# LoRaWAN_Senior_Project_Schematic.net
KiCad netlist of a schematic drawn in Altium Designer
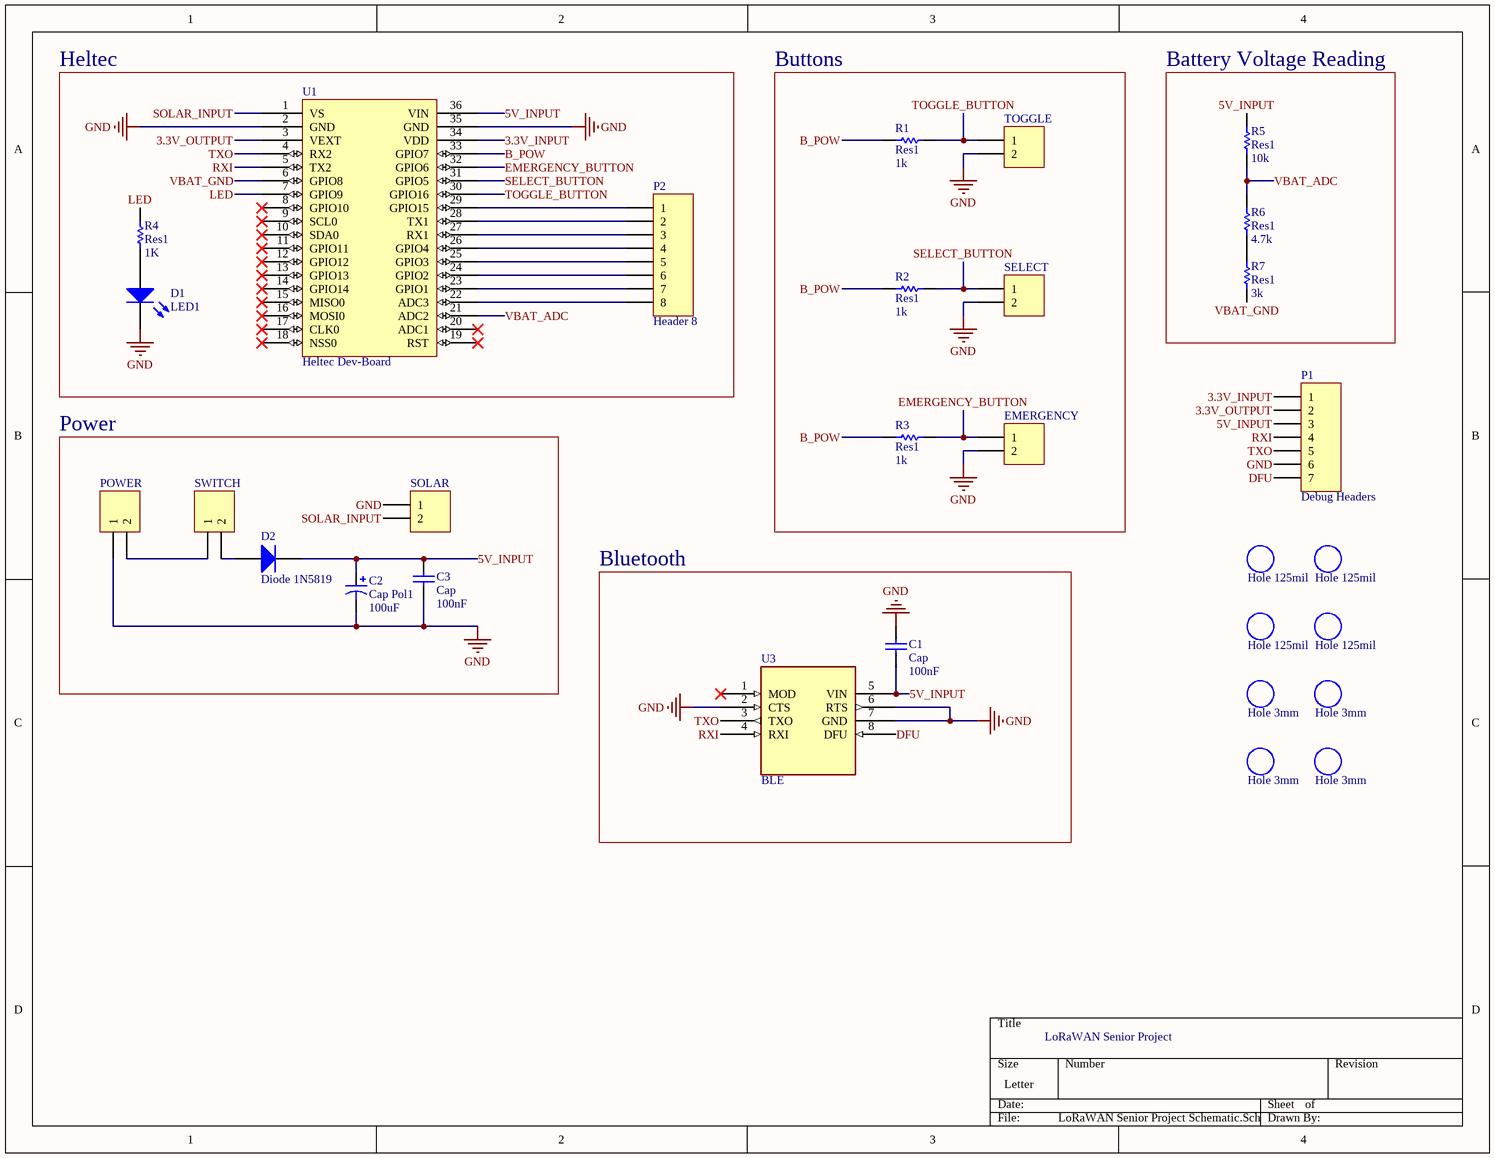
[diagram p0: LoRaWAN Senior Project Schematic.SchDoc]

(export (version "E")
  (design (tool "Eeschema 10.0.6"))
  (components
    (comp (ref "C1")
      (value "Cap")
      (footprint "RAD-0.1")
      (description "Capacitor")
      (fields (field (name "ALTIUM_VALUE") "100nF") (field (name "PUBLISHER") "Altium Limited"))
      (libsource (lib "Miscellaneous Devices") (part "Cap"))
    )
    (comp (ref "C2")
      (value "Cap Pol1")
      (footprint "RAD-0.2")
      (description "Polarized Capacitor (Radial)")
      (fields (field (name "ALTIUM_VALUE") "100uF") (field (name "PUBLISHER") "Altium Limited"))
      (libsource (lib "Miscellaneous Devices") (part "Cap Pol1"))
    )
    (comp (ref "C3")
      (value "Cap")
      (footprint "RAD-0.1")
      (description "Capacitor")
      (fields (field (name "ALTIUM_VALUE") "100nF") (field (name "PUBLISHER") "Altium Limited"))
      (libsource (lib "Miscellaneous Devices") (part "Cap"))
    )
    (comp (ref "D1")
      (value "LED1")
      (footprint "LED-1")
      (description "Typical RED GaAs LED")
      (fields (field (name "PUBLISHER") "Altium Limited"))
      (libsource (lib "Miscellaneous Devices") (part "LED1"))
    )
    (comp (ref "D2")
      (value "Diode 1N5819")
      (footprint "DO-41")
      (description "1 Amp General Purpose Rectifier")
      (fields (field (name "PUBLISHER") "Altium Limited"))
      (libsource (lib "Miscellaneous Devices") (part "Diode 1N4001"))
    )
    (comp (ref "EMERGENCY")
      (value "Button Port")
      (footprint "CON2screw")
      (libsource (lib "ECE Lib 22") (part "Power"))
    )
    (comp (ref "H1")
      (value "Hole 125mil")
      (footprint "Hole 125mil")
      (libsource (lib "ECE Lib 22") (part "Hole 125mil"))
    )
    (comp (ref "H2")
      (value "Hole 125mil")
      (footprint "Hole 125mil")
      (libsource (lib "ECE Lib 22") (part "Hole 125mil"))
    )
    (comp (ref "H3")
      (value "Hole 125mil")
      (footprint "Hole 125mil")
      (libsource (lib "ECE Lib 22") (part "Hole 125mil"))
    )
    (comp (ref "H4")
      (value "Hole 125mil")
      (footprint "Hole 125mil")
      (libsource (lib "ECE Lib 22") (part "Hole 125mil"))
    )
    (comp (ref "H5")
      (value "Hole 3mm")
      (footprint "Hole 3mm")
      (libsource (lib "ECE Lib 22") (part "Hole 3mm"))
    )
    (comp (ref "H6")
      (value "Hole 3mm")
      (footprint "Hole 3mm")
      (libsource (lib "ECE Lib 22") (part "Hole 3mm"))
    )
    (comp (ref "H7")
      (value "Hole 3mm")
      (footprint "Hole 3mm")
      (libsource (lib "ECE Lib 22") (part "Hole 3mm"))
    )
    (comp (ref "H8")
      (value "Hole 3mm")
      (footprint "Hole 3mm")
      (libsource (lib "ECE Lib 22") (part "Hole 3mm"))
    )
    (comp (ref "P1")
      (value "Debug Headers")
      (footprint "HDR1X7")
      (description "Header, 7-Pin")
      (fields (field (name "PUBLISHER") "Altium Limited"))
      (libsource (lib "Miscellaneous Connectors") (part "Header 7"))
    )
    (comp (ref "P2")
      (value "Header 8")
      (footprint "HDR1X8")
      (description "Header, 8-Pin")
      (fields (field (name "PUBLISHER") "Altium Limited"))
      (libsource (lib "Miscellaneous Connectors") (part "Header 8"))
    )
    (comp (ref "POWER") (value "Power Port") (footprint "CON2screw") (libsource (lib "") (part "Power_1")))
    (comp (ref "R1")
      (value "Res1")
      (footprint "RESISTOR")
      (description "Resistor")
      (fields (field (name "ALTIUM_VALUE") "1k") (field (name "PUBLISHER") "Altium Limited"))
      (libsource (lib "Miscellaneous Devices") (part "Res1"))
    )
    (comp (ref "R2")
      (value "Res1")
      (footprint "RESISTOR")
      (description "Resistor")
      (fields (field (name "ALTIUM_VALUE") "1k") (field (name "PUBLISHER") "Altium Limited"))
      (libsource (lib "Miscellaneous Devices") (part "Res1"))
    )
    (comp (ref "R3")
      (value "Res1")
      (footprint "RESISTOR")
      (description "Resistor")
      (fields (field (name "ALTIUM_VALUE") "1k") (field (name "PUBLISHER") "Altium Limited"))
      (libsource (lib "Miscellaneous Devices") (part "Res1"))
    )
    (comp (ref "R4")
      (value "Res1")
      (footprint "AXIAL-0.3")
      (description "Resistor")
      (fields (field (name "ALTIUM_VALUE") "1K") (field (name "PUBLISHER") "Altium Limited"))
      (libsource (lib "Miscellaneous Devices") (part "Res1"))
    )
    (comp (ref "R5")
      (value "Res1")
      (footprint "RESISTOR")
      (description "Resistor")
      (fields (field (name "ALTIUM_VALUE") "10k") (field (name "PUBLISHER") "Altium Limited"))
      (libsource (lib "Miscellaneous Devices") (part "Res1"))
    )
    (comp (ref "R6")
      (value "Res1")
      (footprint "RESISTOR")
      (description "Resistor")
      (fields (field (name "ALTIUM_VALUE") "4.7k") (field (name "PUBLISHER") "Altium Limited"))
      (libsource (lib "Miscellaneous Devices") (part "Res1"))
    )
    (comp (ref "R7")
      (value "Res1")
      (footprint "RESISTOR")
      (description "Resistor")
      (fields (field (name "ALTIUM_VALUE") "3k") (field (name "PUBLISHER") "Altium Limited"))
      (libsource (lib "Miscellaneous Devices") (part "Res1"))
    )
    (comp (ref "SELECT")
      (value "Button Port")
      (footprint "CON2screw")
      (libsource (lib "ECE Lib 22") (part "Power"))
    )
    (comp (ref "SOLAR")
      (value "Solar Port")
      (footprint "CON2screw")
      (libsource (lib "ECE Lib 22") (part "Power"))
    )
    (comp (ref "SWITCH") (value "Switch Port") (footprint "CON2screw") (libsource (lib "") (part "Power_1")))
    (comp (ref "TOGGLE")
      (value "Button Port")
      (footprint "CON2screw")
      (libsource (lib "ECE Lib 22") (part "Power"))
    )
    (comp (ref "U1")
      (value "Heltec Dev-Board")
      (footprint "HELTEC")
      (libsource (lib "Senior Design SCHLIB") (part "Heltec Dev-Board"))
    )
    (comp (ref "U3")
      (value "BLE")
      (footprint "Adafruit BLE")
      (libsource (lib "Senior Design SCHLIB") (part "Adafruit BLE"))
    )
  )
  (nets
    (net (code "1") (name "/3.3V_INPUT") (class "Default")
      (node (ref "P1") (pin "1") (pinfunction "1_1") (pintype "passive"))
      (node (ref "U1") (pin "34") (pinfunction "VDD_34") (pintype "power_in"))
    )
    (net (code "2") (name "/3.3V_OUTPUT") (class "Default")
      (node (ref "P1") (pin "2") (pinfunction "2_2") (pintype "passive"))
      (node (ref "U1") (pin "3") (pinfunction "VEXT_3") (pintype "power_in"))
    )
    (net (code "3") (name "/5V_INPUT") (class "Default")
      (node (ref "C1") (pin "2") (pinfunction "2_2") (pintype "passive"))
      (node (ref "C2") (pin "1") (pinfunction "1_1") (pintype "passive"))
      (node (ref "C3") (pin "2") (pinfunction "2_2") (pintype "passive"))
      (node (ref "D2") (pin "2") (pinfunction "K_2") (pintype "passive"))
      (node (ref "P1") (pin "3") (pinfunction "3_3") (pintype "passive"))
      (node (ref "R5") (pin "2") (pinfunction "2_2") (pintype "passive"))
      (node (ref "U1") (pin "36") (pinfunction "VIN_36") (pintype "power_in"))
      (node (ref "U3") (pin "5") (pinfunction "VIN_5") (pintype "power_in"))
    )
    (net (code "4") (name "/B_POW") (class "Default")
      (node (ref "R1") (pin "1") (pinfunction "1_1") (pintype "passive"))
      (node (ref "R2") (pin "1") (pinfunction "1_1") (pintype "passive"))
      (node (ref "R3") (pin "1") (pinfunction "1_1") (pintype "passive"))
      (node (ref "U1") (pin "33") (pinfunction "GPIO7_33") (pintype "bidirectional"))
    )
    (net (code "5") (name "/DFU") (class "Default")
      (node (ref "P1") (pin "7") (pinfunction "7_7") (pintype "passive"))
      (node (ref "U3") (pin "8") (pinfunction "DFU_8") (pintype "input"))
    )
    (net (code "6") (name "/EMERGENCY_BUTTON") (class "Default")
      (node (ref "EMERGENCY") (pin "1") (pinfunction "1_1") (pintype "passive"))
      (node (ref "R3") (pin "2") (pinfunction "2_2") (pintype "passive"))
      (node (ref "U1") (pin "32") (pinfunction "GPIO6_32") (pintype "bidirectional"))
    )
    (net (code "7") (name "/LED") (class "Default")
      (node (ref "R4") (pin "2") (pinfunction "2_2") (pintype "passive"))
      (node (ref "U1") (pin "7") (pinfunction "GPIO9_7") (pintype "bidirectional"))
    )
    (net (code "8") (name "/RXI") (class "Default")
      (node (ref "P1") (pin "4") (pinfunction "4_4") (pintype "passive"))
      (node (ref "U1") (pin "5") (pinfunction "TX2_5") (pintype "bidirectional"))
      (node (ref "U3") (pin "4") (pinfunction "RXI_4") (pintype "input"))
    )
    (net (code "9") (name "/SELECT_BUTTON") (class "Default")
      (node (ref "R2") (pin "2") (pinfunction "2_2") (pintype "passive"))
      (node (ref "SELECT") (pin "1") (pinfunction "1_1") (pintype "passive"))
      (node (ref "U1") (pin "31") (pinfunction "GPIO5_31") (pintype "bidirectional"))
    )
    (net (code "10") (name "/SOLAR_INPUT") (class "Default")
      (node (ref "SOLAR") (pin "2") (pinfunction "2_2") (pintype "passive"))
      (node (ref "U1") (pin "1") (pinfunction "VS_1") (pintype "power_in"))
    )
    (net (code "11") (name "/TOGGLE_BUTTON") (class "Default")
      (node (ref "R1") (pin "2") (pinfunction "2_2") (pintype "passive"))
      (node (ref "TOGGLE") (pin "1") (pinfunction "1_1") (pintype "passive"))
      (node (ref "U1") (pin "30") (pinfunction "GPIO16_30") (pintype "bidirectional"))
    )
    (net (code "12") (name "/TXO") (class "Default")
      (node (ref "P1") (pin "5") (pinfunction "5_5") (pintype "passive"))
      (node (ref "U1") (pin "4") (pinfunction "RX2_4") (pintype "bidirectional"))
      (node (ref "U3") (pin "3") (pinfunction "TXO_3") (pintype "output"))
    )
    (net (code "13") (name "/VBAT_ADC") (class "Default")
      (node (ref "R5") (pin "1") (pinfunction "1_1") (pintype "passive"))
      (node (ref "R6") (pin "2") (pinfunction "2_2") (pintype "passive"))
      (node (ref "U1") (pin "21") (pinfunction "ADC2_21") (pintype "bidirectional"))
    )
    (net (code "14") (name "/VBAT_GND") (class "Default")
      (node (ref "R7") (pin "1") (pinfunction "1_1") (pintype "passive"))
      (node (ref "U1") (pin "6") (pinfunction "GPIO8_6") (pintype "bidirectional"))
    )
    (net (code "15") (name "GND") (class "Default")
      (node (ref "C1") (pin "1") (pinfunction "1_1") (pintype "passive"))
      (node (ref "C2") (pin "2") (pinfunction "2_2") (pintype "passive"))
      (node (ref "C3") (pin "1") (pinfunction "1_1") (pintype "passive"))
      (node (ref "D1") (pin "2") (pinfunction "K_2") (pintype "passive"))
      (node (ref "EMERGENCY") (pin "2") (pinfunction "2_2") (pintype "passive"))
      (node (ref "P1") (pin "6") (pinfunction "6_6") (pintype "passive"))
      (node (ref "POWER") (pin "1") (pinfunction "1_1") (pintype "passive"))
      (node (ref "SELECT") (pin "2") (pinfunction "2_2") (pintype "passive"))
      (node (ref "SOLAR") (pin "1") (pinfunction "1_1") (pintype "passive"))
      (node (ref "TOGGLE") (pin "2") (pinfunction "2_2") (pintype "passive"))
      (node (ref "U1") (pin "2") (pinfunction "GND_2") (pintype "power_in"))
      (node (ref "U1") (pin "35") (pinfunction "GND_35") (pintype "power_in"))
      (node (ref "U3") (pin "2") (pinfunction "CTS_2") (pintype "input"))
      (node (ref "U3") (pin "6") (pinfunction "RTS_6") (pintype "output"))
      (node (ref "U3") (pin "7") (pinfunction "GND_7") (pintype "power_in"))
    )
    (net (code "16") (name "Net-(D1-A)") (class "Default")
      (node (ref "D1") (pin "1") (pinfunction "A_1") (pintype "passive"))
      (node (ref "R4") (pin "1") (pinfunction "1_1") (pintype "passive"))
    )
    (net (code "17") (name "Net-(D2-A)") (class "Default")
      (node (ref "D2") (pin "1") (pinfunction "A_1") (pintype "passive"))
      (node (ref "SWITCH") (pin "2") (pinfunction "2_2") (pintype "passive"))
    )
    (net (code "18") (name "Net-(POWER-Pad2)") (class "Default")
      (node (ref "POWER") (pin "2") (pinfunction "2_2") (pintype "passive"))
      (node (ref "SWITCH") (pin "1") (pinfunction "1_1") (pintype "passive"))
    )
    (net (code "19") (name "Net-(R6-Pad1)") (class "Default")
      (node (ref "R6") (pin "1") (pinfunction "1_1") (pintype "passive"))
      (node (ref "R7") (pin "2") (pinfunction "2_2") (pintype "passive"))
    )
    (net (code "20") (name "Net-(U1-ADC3)") (class "Default")
      (node (ref "P2") (pin "8") (pinfunction "8_8") (pintype "passive"))
      (node (ref "U1") (pin "22") (pinfunction "ADC3_22") (pintype "bidirectional"))
    )
    (net (code "21") (name "Net-(U1-GPIO1)") (class "Default")
      (node (ref "P2") (pin "7") (pinfunction "7_7") (pintype "passive"))
      (node (ref "U1") (pin "23") (pinfunction "GPIO1_23") (pintype "bidirectional"))
    )
    (net (code "22") (name "Net-(U1-GPIO2)") (class "Default")
      (node (ref "P2") (pin "6") (pinfunction "6_6") (pintype "passive"))
      (node (ref "U1") (pin "24") (pinfunction "GPIO2_24") (pintype "bidirectional"))
    )
    (net (code "23") (name "Net-(U1-GPIO3)") (class "Default")
      (node (ref "P2") (pin "5") (pinfunction "5_5") (pintype "passive"))
      (node (ref "U1") (pin "25") (pinfunction "GPIO3_25") (pintype "bidirectional"))
    )
    (net (code "24") (name "Net-(U1-GPIO4)") (class "Default")
      (node (ref "P2") (pin "4") (pinfunction "4_4") (pintype "passive"))
      (node (ref "U1") (pin "26") (pinfunction "GPIO4_26") (pintype "bidirectional"))
    )
    (net (code "25") (name "Net-(U1-GPIO15)") (class "Default")
      (node (ref "P2") (pin "1") (pinfunction "1_1") (pintype "passive"))
      (node (ref "U1") (pin "29") (pinfunction "GPIO15_29") (pintype "bidirectional"))
    )
    (net (code "26") (name "Net-(U1-RX1)") (class "Default")
      (node (ref "P2") (pin "3") (pinfunction "3_3") (pintype "passive"))
      (node (ref "U1") (pin "27") (pinfunction "RX1_27") (pintype "bidirectional"))
    )
    (net (code "27") (name "Net-(U1-TX1)") (class "Default")
      (node (ref "P2") (pin "2") (pinfunction "2_2") (pintype "passive"))
      (node (ref "U1") (pin "28") (pinfunction "TX1_28") (pintype "bidirectional"))
    )
    (net (code "28") (name "unconnected-(U1-ADC1-Pad20)") (class "Default")
      (node (ref "U1") (pin "20") (pinfunction "ADC1_20") (pintype "bidirectional+no_connect"))
    )
    (net (code "29") (name "unconnected-(U1-CLK0-Pad17)") (class "Default")
      (node (ref "U1") (pin "17") (pinfunction "CLK0_17") (pintype "bidirectional+no_connect"))
    )
    (net (code "30") (name "unconnected-(U1-GPIO10-Pad8)") (class "Default")
      (node (ref "U1") (pin "8") (pinfunction "GPIO10_8") (pintype "bidirectional+no_connect"))
    )
    (net (code "31") (name "unconnected-(U1-GPIO11-Pad11)") (class "Default")
      (node (ref "U1") (pin "11") (pinfunction "GPIO11_11") (pintype "bidirectional+no_connect"))
    )
    (net (code "32") (name "unconnected-(U1-GPIO12-Pad12)") (class "Default")
      (node (ref "U1") (pin "12") (pinfunction "GPIO12_12") (pintype "bidirectional+no_connect"))
    )
    (net (code "33") (name "unconnected-(U1-GPIO13-Pad13)") (class "Default")
      (node (ref "U1") (pin "13") (pinfunction "GPIO13_13") (pintype "bidirectional+no_connect"))
    )
    (net (code "34") (name "unconnected-(U1-GPIO14-Pad14)") (class "Default")
      (node (ref "U1") (pin "14") (pinfunction "GPIO14_14") (pintype "bidirectional+no_connect"))
    )
    (net (code "35") (name "unconnected-(U1-MISO0-Pad15)") (class "Default")
      (node (ref "U1") (pin "15") (pinfunction "MISO0_15") (pintype "bidirectional+no_connect"))
    )
    (net (code "36") (name "unconnected-(U1-MOSI0-Pad16)") (class "Default")
      (node (ref "U1") (pin "16") (pinfunction "MOSI0_16") (pintype "bidirectional+no_connect"))
    )
    (net (code "37") (name "unconnected-(U1-NSS0-Pad18)") (class "Default")
      (node (ref "U1") (pin "18") (pinfunction "NSS0_18") (pintype "bidirectional+no_connect"))
    )
    (net (code "38") (name "unconnected-(U1-RST-Pad19)") (class "Default")
      (node (ref "U1") (pin "19") (pinfunction "RST_19") (pintype "bidirectional+no_connect"))
    )
    (net (code "39") (name "unconnected-(U1-SCL0-Pad9)") (class "Default")
      (node (ref "U1") (pin "9") (pinfunction "SCL0_9") (pintype "bidirectional+no_connect"))
    )
    (net (code "40") (name "unconnected-(U1-SDA0-Pad10)") (class "Default")
      (node (ref "U1") (pin "10") (pinfunction "SDA0_10") (pintype "bidirectional+no_connect"))
    )
    (net (code "41") (name "unconnected-(U3-MOD-Pad1)") (class "Default")
      (node (ref "U3") (pin "1") (pinfunction "MOD_1") (pintype "input+no_connect"))
    )
  )
)
